# CAN-WiFi-GW-DevBoard.net
KiCad netlist of a schematic drawn in EAGLE
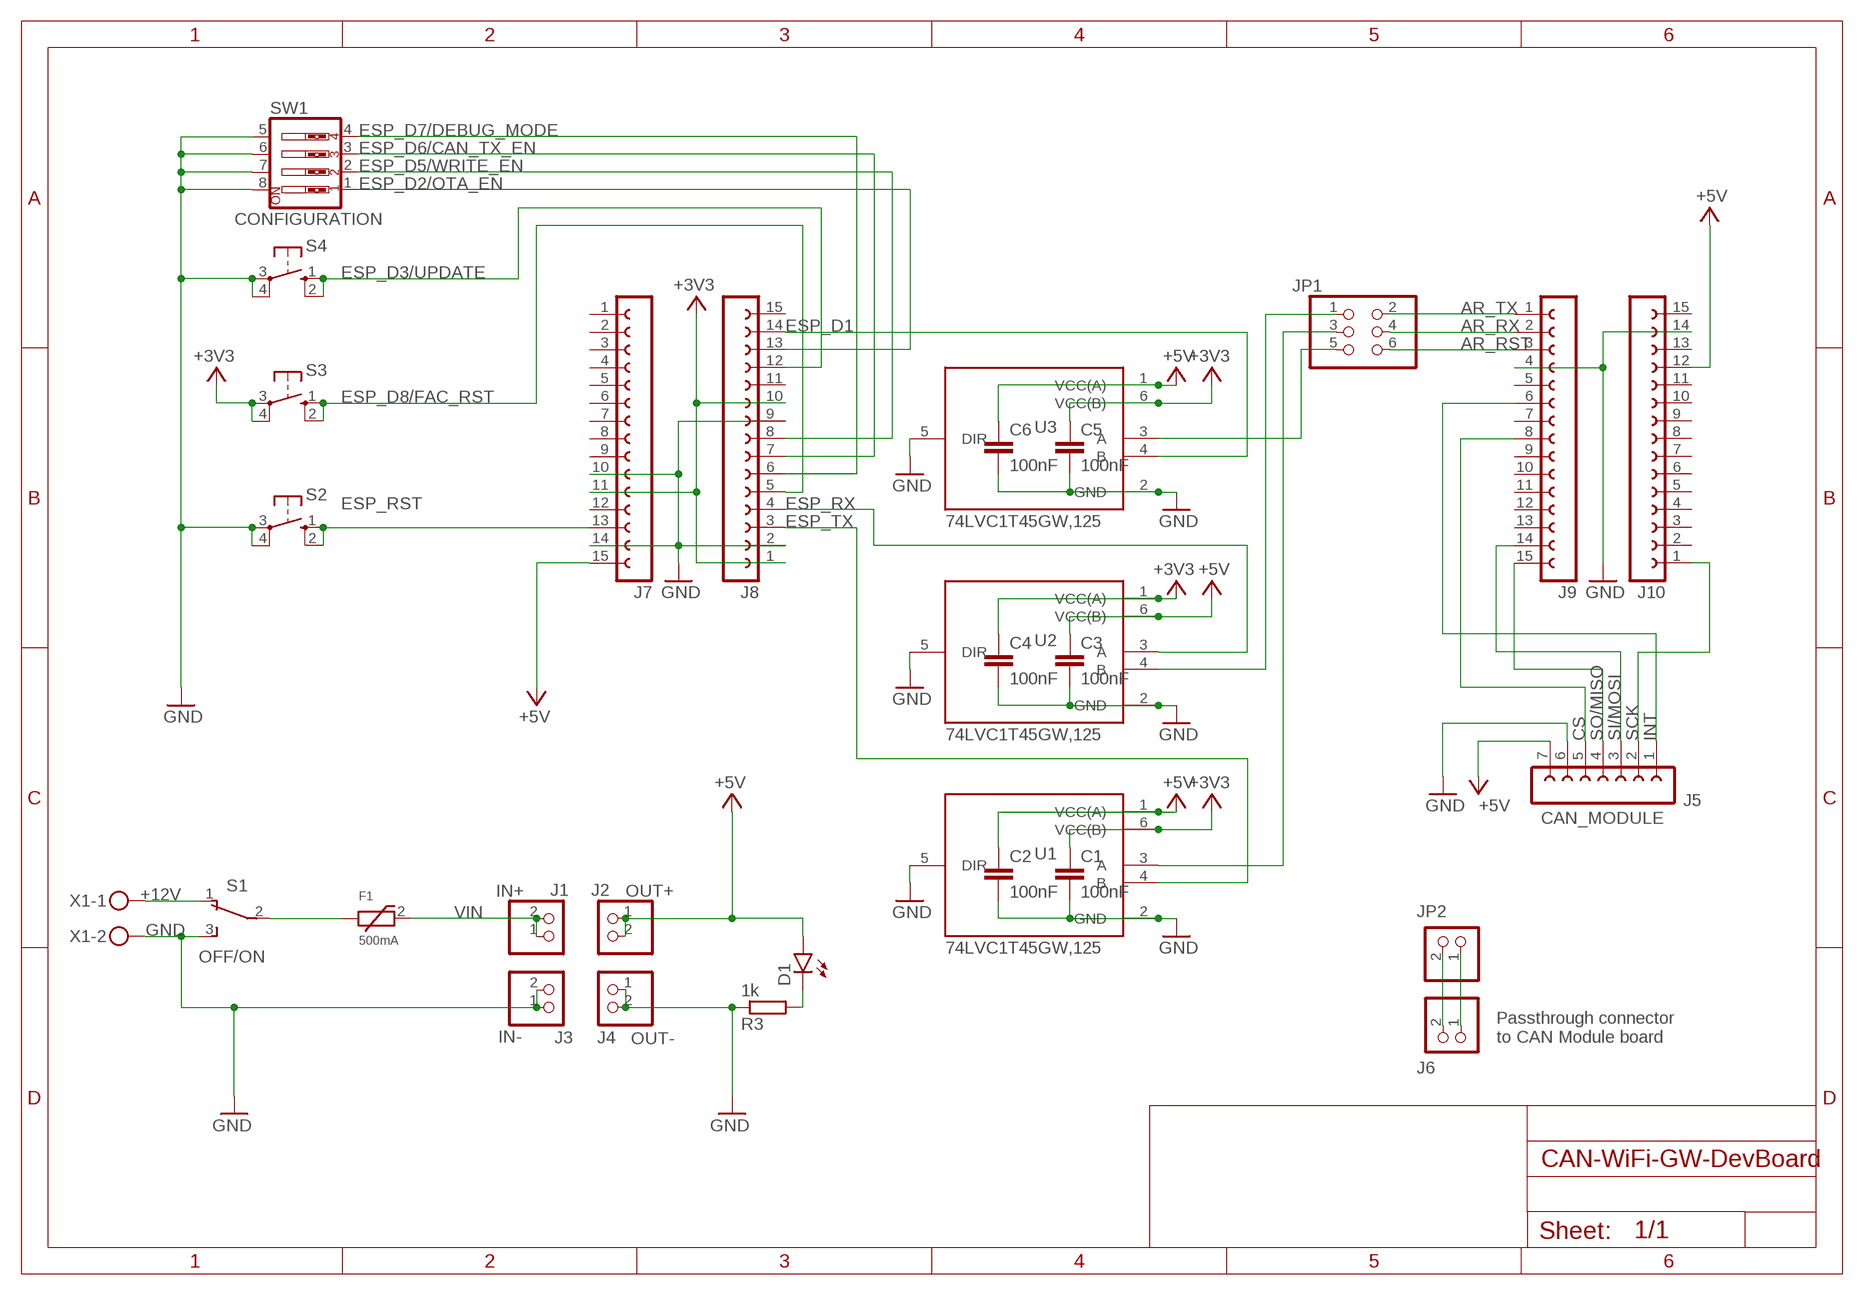
[diagram p0: schematic, sheet 1]

(export (version "E")
  (design (tool "Eeschema 10.0.6"))
  (components
    (comp (ref "C1")
      (value "100nF")
      (footprint "eagle-import:C1206")
      (libsource (lib "eagle-import") (part "C-EUC1206"))
    )
    (comp (ref "C2")
      (value "100nF")
      (footprint "eagle-import:C1206")
      (libsource (lib "eagle-import") (part "C-EUC1206"))
    )
    (comp (ref "C3")
      (value "100nF")
      (footprint "eagle-import:C1206")
      (libsource (lib "eagle-import") (part "C-EUC1206"))
    )
    (comp (ref "C4")
      (value "100nF")
      (footprint "eagle-import:C1206")
      (libsource (lib "eagle-import") (part "C-EUC1206"))
    )
    (comp (ref "C5")
      (value "100nF")
      (footprint "eagle-import:C1206")
      (libsource (lib "eagle-import") (part "C-EUC1206"))
    )
    (comp (ref "C6")
      (value "100nF")
      (footprint "eagle-import:C1206")
      (libsource (lib "eagle-import") (part "C-EUC1206"))
    )
    (comp (ref "D1")
      (value "LEDSML0805")
      (footprint "eagle-import:SML0805")
      (libsource (lib "eagle-import") (part "LEDSML0805"))
    )
    (comp (ref "F1")
      (value "500mA")
      (footprint "eagle-import:FSMD050-1210-R")
      (libsource (lib "eagle-import") (part "PTC-FUSE"))
    )
    (comp (ref "J1")
      (value "IN+")
      (footprint "eagle-import:1X02")
      (libsource (lib "eagle-import") (part "PINHD-1X2"))
    )
    (comp (ref "J2")
      (value "OUT+")
      (footprint "eagle-import:1X02")
      (libsource (lib "eagle-import") (part "PINHD-1X2"))
    )
    (comp (ref "J3")
      (value "IN-")
      (footprint "eagle-import:1X02")
      (libsource (lib "eagle-import") (part "PINHD-1X2"))
    )
    (comp (ref "J4")
      (value "OUT-")
      (footprint "eagle-import:1X02")
      (libsource (lib "eagle-import") (part "PINHD-1X2"))
    )
    (comp (ref "J5")
      (value "CAN_MODULE")
      (footprint "eagle-import:FE07")
      (libsource (lib "eagle-import") (part "FE07-1"))
    )
    (comp (ref "J6")
      (value "PINHD-1X2")
      (footprint "eagle-import:1X02")
      (libsource (lib "eagle-import") (part "PINHD-1X2"))
    )
    (comp (ref "J7")
      (value "FE15-1")
      (footprint "eagle-import:FE15")
      (libsource (lib "eagle-import") (part "FE15-1"))
    )
    (comp (ref "J8")
      (value "FE15-1")
      (footprint "eagle-import:FE15")
      (libsource (lib "eagle-import") (part "FE15-1"))
    )
    (comp (ref "J9")
      (value "FE15-1")
      (footprint "eagle-import:FE15")
      (libsource (lib "eagle-import") (part "FE15-1"))
    )
    (comp (ref "J10")
      (value "FE15-1")
      (footprint "eagle-import:FE15")
      (libsource (lib "eagle-import") (part "FE15-1"))
    )
    (comp (ref "JP1")
      (value "PINHD-2X3")
      (footprint "eagle-import:2X03")
      (libsource (lib "eagle-import") (part "PINHD-2X3"))
    )
    (comp (ref "JP2")
      (value "PINHD-1X2")
      (footprint "eagle-import:1X02")
      (libsource (lib "eagle-import") (part "PINHD-1X2"))
    )
    (comp (ref "R3")
      (value "1k")
      (footprint "eagle-import:R0805")
      (libsource (lib "eagle-import") (part "R-EU_R0805"))
    )
    (comp (ref "S1")
      (value "OFF/ON")
      (footprint "eagle-import:TL3XPO")
      (libsource (lib "eagle-import") (part "TL36PO"))
    )
    (comp (ref "S2")
      (value "10-XX")
      (footprint "eagle-import:B3F-10XX")
      (fields (field (name "MPN") "B3F-1000"))
      (libsource (lib "eagle-import") (part "10-XX"))
    )
    (comp (ref "S3")
      (value "10-XX")
      (footprint "eagle-import:B3F-10XX")
      (fields (field (name "MPN") "B3F-1000"))
      (libsource (lib "eagle-import") (part "10-XX"))
    )
    (comp (ref "S4")
      (value "10-XX")
      (footprint "eagle-import:B3F-10XX")
      (fields (field (name "MPN") "B3F-1000"))
      (libsource (lib "eagle-import") (part "10-XX"))
    )
    (comp (ref "SW1")
      (value "CONFIGURATION")
      (footprint "eagle-import:EDG-04")
      (libsource (lib "eagle-import") (part "SW_DIP-4"))
    )
    (comp (ref "U1")
      (value "74LVC1T45GW,125")
      (footprint "eagle-import:SOP65P210X110-6N")
      (fields (field (name "MF") "Nexperia USA Inc."))
      (libsource (lib "eagle-import") (part "74LVC1T45GW,125"))
    )
    (comp (ref "U2")
      (value "74LVC1T45GW,125")
      (footprint "eagle-import:SOP65P210X110-6N")
      (fields (field (name "MF") "Nexperia USA Inc."))
      (libsource (lib "eagle-import") (part "74LVC1T45GW,125"))
    )
    (comp (ref "U3")
      (value "74LVC1T45GW,125")
      (footprint "eagle-import:SOP65P210X110-6N")
      (fields (field (name "MF") "Nexperia USA Inc."))
      (libsource (lib "eagle-import") (part "74LVC1T45GW,125"))
    )
    (comp (ref "X1")
      (value "MKDSN1,5/2-5,08")
      (footprint "eagle-import:MKDSN1,5_2-5,08")
      (libsource (lib "eagle-import") (part "MKDSN1,5/2-5,08"))
    )
  )
  (nets
    (net (code "1") (name "+3V3") (class "Default")
      (node (ref "C1") (pin "1") (pinfunction "1_1") (pintype "passive"))
      (node (ref "C4") (pin "1") (pinfunction "1_1") (pintype "passive"))
      (node (ref "C5") (pin "1") (pinfunction "1_1") (pintype "passive"))
      (node (ref "J7") (pin "11") (pinfunction "11_11") (pintype "passive"))
      (node (ref "J8") (pin "1") (pinfunction "1_1") (pintype "passive"))
      (node (ref "J8") (pin "10") (pinfunction "10_10") (pintype "passive"))
      (node (ref "S3") (pin "3") (pinfunction "P_3") (pintype "passive"))
      (node (ref "S3") (pin "4") (pinfunction "P1_4") (pintype "passive"))
      (node (ref "U1") (pin "6") (pinfunction "VCC(B)_6") (pintype "power_in"))
      (node (ref "U2") (pin "1") (pinfunction "VCC(A)_1") (pintype "power_in"))
      (node (ref "U3") (pin "6") (pinfunction "VCC(B)_6") (pintype "power_in"))
    )
    (net (code "2") (name "+5V") (class "Default")
      (node (ref "C2") (pin "1") (pinfunction "1_1") (pintype "passive"))
      (node (ref "C3") (pin "1") (pinfunction "1_1") (pintype "passive"))
      (node (ref "C6") (pin "1") (pinfunction "1_1") (pintype "passive"))
      (node (ref "D1") (pin "A") (pinfunction "A_A") (pintype "passive"))
      (node (ref "J10") (pin "12") (pinfunction "12_12") (pintype "passive"))
      (node (ref "J2") (pin "1") (pinfunction "1_1") (pintype "passive"))
      (node (ref "J2") (pin "2") (pinfunction "2_2") (pintype "passive"))
      (node (ref "J5") (pin "7") (pinfunction "7_7") (pintype "passive"))
      (node (ref "J7") (pin "15") (pinfunction "15_15") (pintype "passive"))
      (node (ref "U1") (pin "1") (pinfunction "VCC(A)_1") (pintype "power_in"))
      (node (ref "U2") (pin "6") (pinfunction "VCC(B)_6") (pintype "power_in"))
      (node (ref "U3") (pin "1") (pinfunction "VCC(A)_1") (pintype "power_in"))
    )
    (net (code "3") (name "/+12V") (class "Default")
      (node (ref "S1") (pin "1") (pinfunction "O_1") (pintype "passive"))
      (node (ref "X1") (pin "1") (pinfunction "KL_1") (pintype "passive"))
    )
    (net (code "4") (name "/AR_RST") (class "Default")
      (node (ref "J9") (pin "3") (pinfunction "3_3") (pintype "passive"))
      (node (ref "JP1") (pin "6") (pinfunction "6_6") (pintype "passive"))
    )
    (net (code "5") (name "/AR_RX") (class "Default")
      (node (ref "J9") (pin "2") (pinfunction "2_2") (pintype "passive"))
      (node (ref "JP1") (pin "4") (pinfunction "4_4") (pintype "passive"))
    )
    (net (code "6") (name "/AR_TX") (class "Default")
      (node (ref "J9") (pin "1") (pinfunction "1_1") (pintype "passive"))
      (node (ref "JP1") (pin "2") (pinfunction "2_2") (pintype "passive"))
    )
    (net (code "7") (name "/CS") (class "Default")
      (node (ref "J5") (pin "5") (pinfunction "5_5") (pintype "passive"))
      (node (ref "J9") (pin "8") (pinfunction "8_8") (pintype "passive"))
    )
    (net (code "8") (name "/ESP_D1") (class "Default")
      (node (ref "J8") (pin "14") (pinfunction "14_14") (pintype "passive"))
      (node (ref "U3") (pin "4") (pinfunction "B_4") (pintype "bidirectional"))
    )
    (net (code "9") (name "/ESP_D2{slash}OTA_EN") (class "Default")
      (node (ref "J8") (pin "13") (pinfunction "13_13") (pintype "passive"))
      (node (ref "SW1") (pin "1") (pinfunction "1_1") (pintype "passive"))
    )
    (net (code "10") (name "/ESP_D3{slash}UPDATE") (class "Default")
      (node (ref "J8") (pin "12") (pinfunction "12_12") (pintype "passive"))
      (node (ref "S4") (pin "1") (pinfunction "S_1") (pintype "passive"))
      (node (ref "S4") (pin "2") (pinfunction "S1_2") (pintype "passive"))
    )
    (net (code "11") (name "/ESP_D5{slash}WRITE_EN") (class "Default")
      (node (ref "J8") (pin "8") (pinfunction "8_8") (pintype "passive"))
      (node (ref "SW1") (pin "2") (pinfunction "2_2") (pintype "passive"))
    )
    (net (code "12") (name "/ESP_D6{slash}CAN_TX_EN") (class "Default")
      (node (ref "J8") (pin "7") (pinfunction "7_7") (pintype "passive"))
      (node (ref "SW1") (pin "3") (pinfunction "3_3") (pintype "passive"))
    )
    (net (code "13") (name "/ESP_D7{slash}DEBUG_MODE") (class "Default")
      (node (ref "J8") (pin "6") (pinfunction "6_6") (pintype "passive"))
      (node (ref "SW1") (pin "4") (pinfunction "4_4") (pintype "passive"))
    )
    (net (code "14") (name "/ESP_D8{slash}FAC_RST") (class "Default")
      (node (ref "J8") (pin "5") (pinfunction "5_5") (pintype "passive"))
      (node (ref "S3") (pin "1") (pinfunction "S_1") (pintype "passive"))
      (node (ref "S3") (pin "2") (pinfunction "S1_2") (pintype "passive"))
    )
    (net (code "15") (name "/ESP_RST") (class "Default")
      (node (ref "J7") (pin "13") (pinfunction "13_13") (pintype "passive"))
      (node (ref "S2") (pin "1") (pinfunction "S_1") (pintype "passive"))
      (node (ref "S2") (pin "2") (pinfunction "S1_2") (pintype "passive"))
    )
    (net (code "16") (name "/ESP_RX") (class "Default")
      (node (ref "J8") (pin "4") (pinfunction "4_4") (pintype "passive"))
      (node (ref "U2") (pin "3") (pinfunction "A_3") (pintype "bidirectional"))
    )
    (net (code "17") (name "/ESP_TX") (class "Default")
      (node (ref "J8") (pin "3") (pinfunction "3_3") (pintype "passive"))
      (node (ref "U1") (pin "4") (pinfunction "B_4") (pintype "bidirectional"))
    )
    (net (code "18") (name "/INT") (class "Default")
      (node (ref "J5") (pin "1") (pinfunction "1_1") (pintype "passive"))
      (node (ref "J9") (pin "6") (pinfunction "6_6") (pintype "passive"))
    )
    (net (code "19") (name "/SCK") (class "Default")
      (node (ref "J10") (pin "1") (pinfunction "1_1") (pintype "passive"))
      (node (ref "J5") (pin "2") (pinfunction "2_2") (pintype "passive"))
    )
    (net (code "20") (name "/SI{slash}MOSI") (class "Default")
      (node (ref "J5") (pin "3") (pinfunction "3_3") (pintype "passive"))
      (node (ref "J9") (pin "14") (pinfunction "14_14") (pintype "passive"))
    )
    (net (code "21") (name "/SO{slash}MISO") (class "Default")
      (node (ref "J5") (pin "4") (pinfunction "4_4") (pintype "passive"))
      (node (ref "J9") (pin "15") (pinfunction "15_15") (pintype "passive"))
    )
    (net (code "22") (name "/VIN") (class "Default")
      (node (ref "F1") (pin "2") (pinfunction "2_2") (pintype "passive"))
      (node (ref "J1") (pin "1") (pinfunction "1_1") (pintype "passive"))
      (node (ref "J1") (pin "2") (pinfunction "2_2") (pintype "passive"))
    )
    (net (code "23") (name "GND") (class "Default")
      (node (ref "C1") (pin "2") (pinfunction "2_2") (pintype "passive"))
      (node (ref "C2") (pin "2") (pinfunction "2_2") (pintype "passive"))
      (node (ref "C3") (pin "2") (pinfunction "2_2") (pintype "passive"))
      (node (ref "C4") (pin "2") (pinfunction "2_2") (pintype "passive"))
      (node (ref "C5") (pin "2") (pinfunction "2_2") (pintype "passive"))
      (node (ref "C6") (pin "2") (pinfunction "2_2") (pintype "passive"))
      (node (ref "J10") (pin "14") (pinfunction "14_14") (pintype "passive"))
      (node (ref "J3") (pin "1") (pinfunction "1_1") (pintype "passive"))
      (node (ref "J3") (pin "2") (pinfunction "2_2") (pintype "passive"))
      (node (ref "J4") (pin "1") (pinfunction "1_1") (pintype "passive"))
      (node (ref "J4") (pin "2") (pinfunction "2_2") (pintype "passive"))
      (node (ref "J5") (pin "6") (pinfunction "6_6") (pintype "passive"))
      (node (ref "J7") (pin "10") (pinfunction "10_10") (pintype "passive"))
      (node (ref "J7") (pin "14") (pinfunction "14_14") (pintype "passive"))
      (node (ref "J8") (pin "2") (pinfunction "2_2") (pintype "passive"))
      (node (ref "J8") (pin "9") (pinfunction "9_9") (pintype "passive"))
      (node (ref "J9") (pin "4") (pinfunction "4_4") (pintype "passive"))
      (node (ref "R3") (pin "1") (pinfunction "1_1") (pintype "passive"))
      (node (ref "S1") (pin "3") (pinfunction "S_3") (pintype "passive"))
      (node (ref "S2") (pin "3") (pinfunction "P_3") (pintype "passive"))
      (node (ref "S2") (pin "4") (pinfunction "P1_4") (pintype "passive"))
      (node (ref "S4") (pin "3") (pinfunction "P_3") (pintype "passive"))
      (node (ref "S4") (pin "4") (pinfunction "P1_4") (pintype "passive"))
      (node (ref "SW1") (pin "5") (pinfunction "5_5") (pintype "passive"))
      (node (ref "SW1") (pin "6") (pinfunction "6_6") (pintype "passive"))
      (node (ref "SW1") (pin "7") (pinfunction "7_7") (pintype "passive"))
      (node (ref "SW1") (pin "8") (pinfunction "8_8") (pintype "passive"))
      (node (ref "U1") (pin "2") (pinfunction "GND_2") (pintype "power_in"))
      (node (ref "U1") (pin "5") (pinfunction "DIR_5") (pintype "input"))
      (node (ref "U2") (pin "2") (pinfunction "GND_2") (pintype "power_in"))
      (node (ref "U2") (pin "5") (pinfunction "DIR_5") (pintype "input"))
      (node (ref "U3") (pin "2") (pinfunction "GND_2") (pintype "power_in"))
      (node (ref "U3") (pin "5") (pinfunction "DIR_5") (pintype "input"))
      (node (ref "X1") (pin "2") (pinfunction "KL_2") (pintype "passive"))
    )
    (net (code "24") (name "Net-(D1-PadC)") (class "Default")
      (node (ref "D1") (pin "C") (pinfunction "C_C") (pintype "passive"))
      (node (ref "R3") (pin "2") (pinfunction "2_2") (pintype "passive"))
    )
    (net (code "25") (name "Net-(J6-Pad1)") (class "Default")
      (node (ref "J6") (pin "1") (pinfunction "1_1") (pintype "passive"))
      (node (ref "JP2") (pin "1") (pinfunction "1_1") (pintype "passive"))
    )
    (net (code "26") (name "Net-(J6-Pad2)") (class "Default")
      (node (ref "J6") (pin "2") (pinfunction "2_2") (pintype "passive"))
      (node (ref "JP2") (pin "2") (pinfunction "2_2") (pintype "passive"))
    )
    (net (code "27") (name "Net-(S1-P)") (class "Default")
      (node (ref "F1") (pin "1") (pinfunction "1_1") (pintype "passive"))
      (node (ref "S1") (pin "2") (pinfunction "P_2") (pintype "passive"))
    )
    (net (code "28") (name "Net-(U1-A)") (class "Default")
      (node (ref "JP1") (pin "3") (pinfunction "3_3") (pintype "passive"))
      (node (ref "U1") (pin "3") (pinfunction "A_3") (pintype "bidirectional"))
    )
    (net (code "29") (name "Net-(U2-B)") (class "Default")
      (node (ref "JP1") (pin "1") (pinfunction "1_1") (pintype "passive"))
      (node (ref "U2") (pin "4") (pinfunction "B_4") (pintype "bidirectional"))
    )
    (net (code "30") (name "Net-(U3-A)") (class "Default")
      (node (ref "JP1") (pin "5") (pinfunction "5_5") (pintype "passive"))
      (node (ref "U3") (pin "3") (pinfunction "A_3") (pintype "bidirectional"))
    )
    (net (code "31") (name "unconnected-(J7-Pad1)") (class "Default")
      (node (ref "J7") (pin "1") (pinfunction "1_1") (pintype "passive"))
    )
    (net (code "32") (name "unconnected-(J7-Pad2)") (class "Default")
      (node (ref "J7") (pin "2") (pinfunction "2_2") (pintype "passive"))
    )
    (net (code "33") (name "unconnected-(J7-Pad3)") (class "Default")
      (node (ref "J7") (pin "3") (pinfunction "3_3") (pintype "passive"))
    )
    (net (code "34") (name "unconnected-(J7-Pad4)") (class "Default")
      (node (ref "J7") (pin "4") (pinfunction "4_4") (pintype "passive"))
    )
    (net (code "35") (name "unconnected-(J7-Pad5)") (class "Default")
      (node (ref "J7") (pin "5") (pinfunction "5_5") (pintype "passive"))
    )
    (net (code "36") (name "unconnected-(J7-Pad6)") (class "Default")
      (node (ref "J7") (pin "6") (pinfunction "6_6") (pintype "passive"))
    )
    (net (code "37") (name "unconnected-(J7-Pad7)") (class "Default")
      (node (ref "J7") (pin "7") (pinfunction "7_7") (pintype "passive"))
    )
    (net (code "38") (name "unconnected-(J7-Pad8)") (class "Default")
      (node (ref "J7") (pin "8") (pinfunction "8_8") (pintype "passive"))
    )
    (net (code "39") (name "unconnected-(J7-Pad9)") (class "Default")
      (node (ref "J7") (pin "9") (pinfunction "9_9") (pintype "passive"))
    )
    (net (code "40") (name "unconnected-(J7-Pad12)") (class "Default")
      (node (ref "J7") (pin "12") (pinfunction "12_12") (pintype "passive"))
    )
    (net (code "41") (name "unconnected-(J8-Pad11)") (class "Default")
      (node (ref "J8") (pin "11") (pinfunction "11_11") (pintype "passive"))
    )
    (net (code "42") (name "unconnected-(J8-Pad15)") (class "Default")
      (node (ref "J8") (pin "15") (pinfunction "15_15") (pintype "passive"))
    )
    (net (code "43") (name "unconnected-(J9-Pad5)") (class "Default")
      (node (ref "J9") (pin "5") (pinfunction "5_5") (pintype "passive"))
    )
    (net (code "44") (name "unconnected-(J9-Pad7)") (class "Default")
      (node (ref "J9") (pin "7") (pinfunction "7_7") (pintype "passive"))
    )
    (net (code "45") (name "unconnected-(J9-Pad9)") (class "Default")
      (node (ref "J9") (pin "9") (pinfunction "9_9") (pintype "passive"))
    )
    (net (code "46") (name "unconnected-(J9-Pad10)") (class "Default")
      (node (ref "J9") (pin "10") (pinfunction "10_10") (pintype "passive"))
    )
    (net (code "47") (name "unconnected-(J9-Pad11)") (class "Default")
      (node (ref "J9") (pin "11") (pinfunction "11_11") (pintype "passive"))
    )
    (net (code "48") (name "unconnected-(J9-Pad12)") (class "Default")
      (node (ref "J9") (pin "12") (pinfunction "12_12") (pintype "passive"))
    )
    (net (code "49") (name "unconnected-(J9-Pad13)") (class "Default")
      (node (ref "J9") (pin "13") (pinfunction "13_13") (pintype "passive"))
    )
    (net (code "50") (name "unconnected-(J10-Pad2)") (class "Default")
      (node (ref "J10") (pin "2") (pinfunction "2_2") (pintype "passive"))
    )
    (net (code "51") (name "unconnected-(J10-Pad3)") (class "Default")
      (node (ref "J10") (pin "3") (pinfunction "3_3") (pintype "passive"))
    )
    (net (code "52") (name "unconnected-(J10-Pad4)") (class "Default")
      (node (ref "J10") (pin "4") (pinfunction "4_4") (pintype "passive"))
    )
    (net (code "53") (name "unconnected-(J10-Pad5)") (class "Default")
      (node (ref "J10") (pin "5") (pinfunction "5_5") (pintype "passive"))
    )
    (net (code "54") (name "unconnected-(J10-Pad6)") (class "Default")
      (node (ref "J10") (pin "6") (pinfunction "6_6") (pintype "passive"))
    )
    (net (code "55") (name "unconnected-(J10-Pad7)") (class "Default")
      (node (ref "J10") (pin "7") (pinfunction "7_7") (pintype "passive"))
    )
    (net (code "56") (name "unconnected-(J10-Pad8)") (class "Default")
      (node (ref "J10") (pin "8") (pinfunction "8_8") (pintype "passive"))
    )
    (net (code "57") (name "unconnected-(J10-Pad9)") (class "Default")
      (node (ref "J10") (pin "9") (pinfunction "9_9") (pintype "passive"))
    )
    (net (code "58") (name "unconnected-(J10-Pad10)") (class "Default")
      (node (ref "J10") (pin "10") (pinfunction "10_10") (pintype "passive"))
    )
    (net (code "59") (name "unconnected-(J10-Pad11)") (class "Default")
      (node (ref "J10") (pin "11") (pinfunction "11_11") (pintype "passive"))
    )
    (net (code "60") (name "unconnected-(J10-Pad13)") (class "Default")
      (node (ref "J10") (pin "13") (pinfunction "13_13") (pintype "passive"))
    )
    (net (code "61") (name "unconnected-(J10-Pad15)") (class "Default")
      (node (ref "J10") (pin "15") (pinfunction "15_15") (pintype "passive"))
    )
  )
)
